# 5-VOL_CHECK.net
KiCad netlist of a schematic drawn in Altium Designer
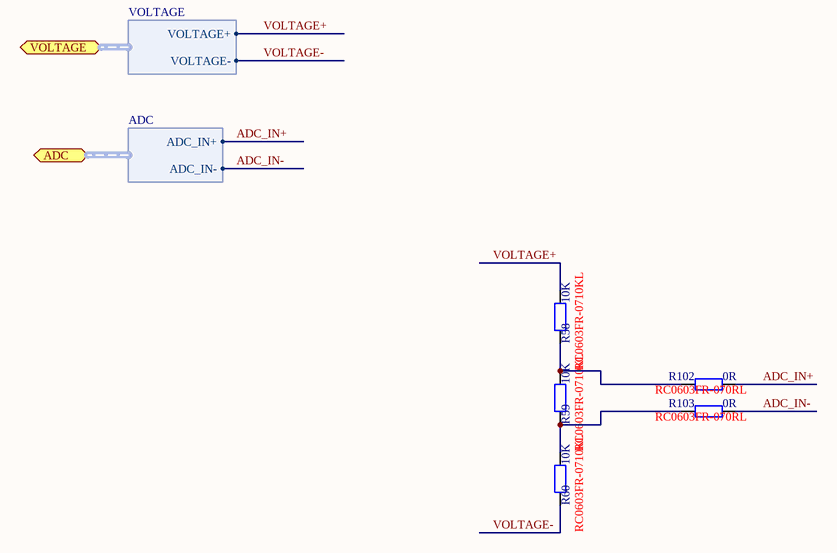
[diagram p0: 5-VOL_CHECK.SchDoc]

(export (version "E")
  (design (tool "Eeschema 10.0.6"))
  (components
    (comp (ref "R58")
      (value "10K")
      (footprint "CC0603")
      (description "Resistor")
      (fields (field (name "TYPE NO.") "RC0603FR-0710KL"))
      (libsource (lib "Miscellaneous Devices") (part "Res2"))
    )
    (comp (ref "R59")
      (value "10K")
      (footprint "CC0603")
      (description "Resistor")
      (fields (field (name "TYPE NO.") "RC0603FR-0710KL"))
      (libsource (lib "Miscellaneous Devices") (part "Res2"))
    )
    (comp (ref "R60")
      (value "10K")
      (footprint "CC0603")
      (description "Resistor")
      (fields (field (name "TYPE NO.") "RC0603FR-0710KL"))
      (libsource (lib "Miscellaneous Devices") (part "Res2"))
    )
    (comp (ref "R102")
      (value "0R")
      (footprint "CC0603")
      (description "Resistor")
      (fields (field (name "TYPE NO.") "RC0603FR-070RL"))
      (libsource (lib "") (part "Res2_1"))
    )
    (comp (ref "R103")
      (value "0R")
      (footprint "CC0603")
      (description "Resistor")
      (fields (field (name "TYPE NO.") "RC0603FR-070RL"))
      (libsource (lib "") (part "Res2_1"))
    )
  )
  (nets
    (net (code "3") (name "/ADC_IN+") (class "Default")
      (node (ref "R102") (pin "1") (pinfunction "1_1") (pintype "passive"))
    )
    (net (code "4") (name "/ADC_IN-") (class "Default")
      (node (ref "R103") (pin "1") (pinfunction "1_1") (pintype "passive"))
    )
    (net (code "5") (name "/VOLTAGE+") (class "Default")
      (node (ref "R58") (pin "1") (pinfunction "1_1") (pintype "passive"))
    )
    (net (code "6") (name "/VOLTAGE-") (class "Default")
      (node (ref "R60") (pin "2") (pinfunction "2_2") (pintype "passive"))
    )
    (net (code "9") (name "Net-(R102-Pad2)") (class "Default")
      (node (ref "R102") (pin "2") (pinfunction "2_2") (pintype "passive"))
      (node (ref "R58") (pin "2") (pinfunction "2_2") (pintype "passive"))
      (node (ref "R59") (pin "1") (pinfunction "1_1") (pintype "passive"))
    )
    (net (code "10") (name "Net-(R103-Pad2)") (class "Default")
      (node (ref "R103") (pin "2") (pinfunction "2_2") (pintype "passive"))
      (node (ref "R59") (pin "2") (pinfunction "2_2") (pintype "passive"))
      (node (ref "R60") (pin "1") (pinfunction "1_1") (pintype "passive"))
    )
  )
)
